# 512_outin_arduino.net
KiCad netlist of a schematic drawn in EAGLE
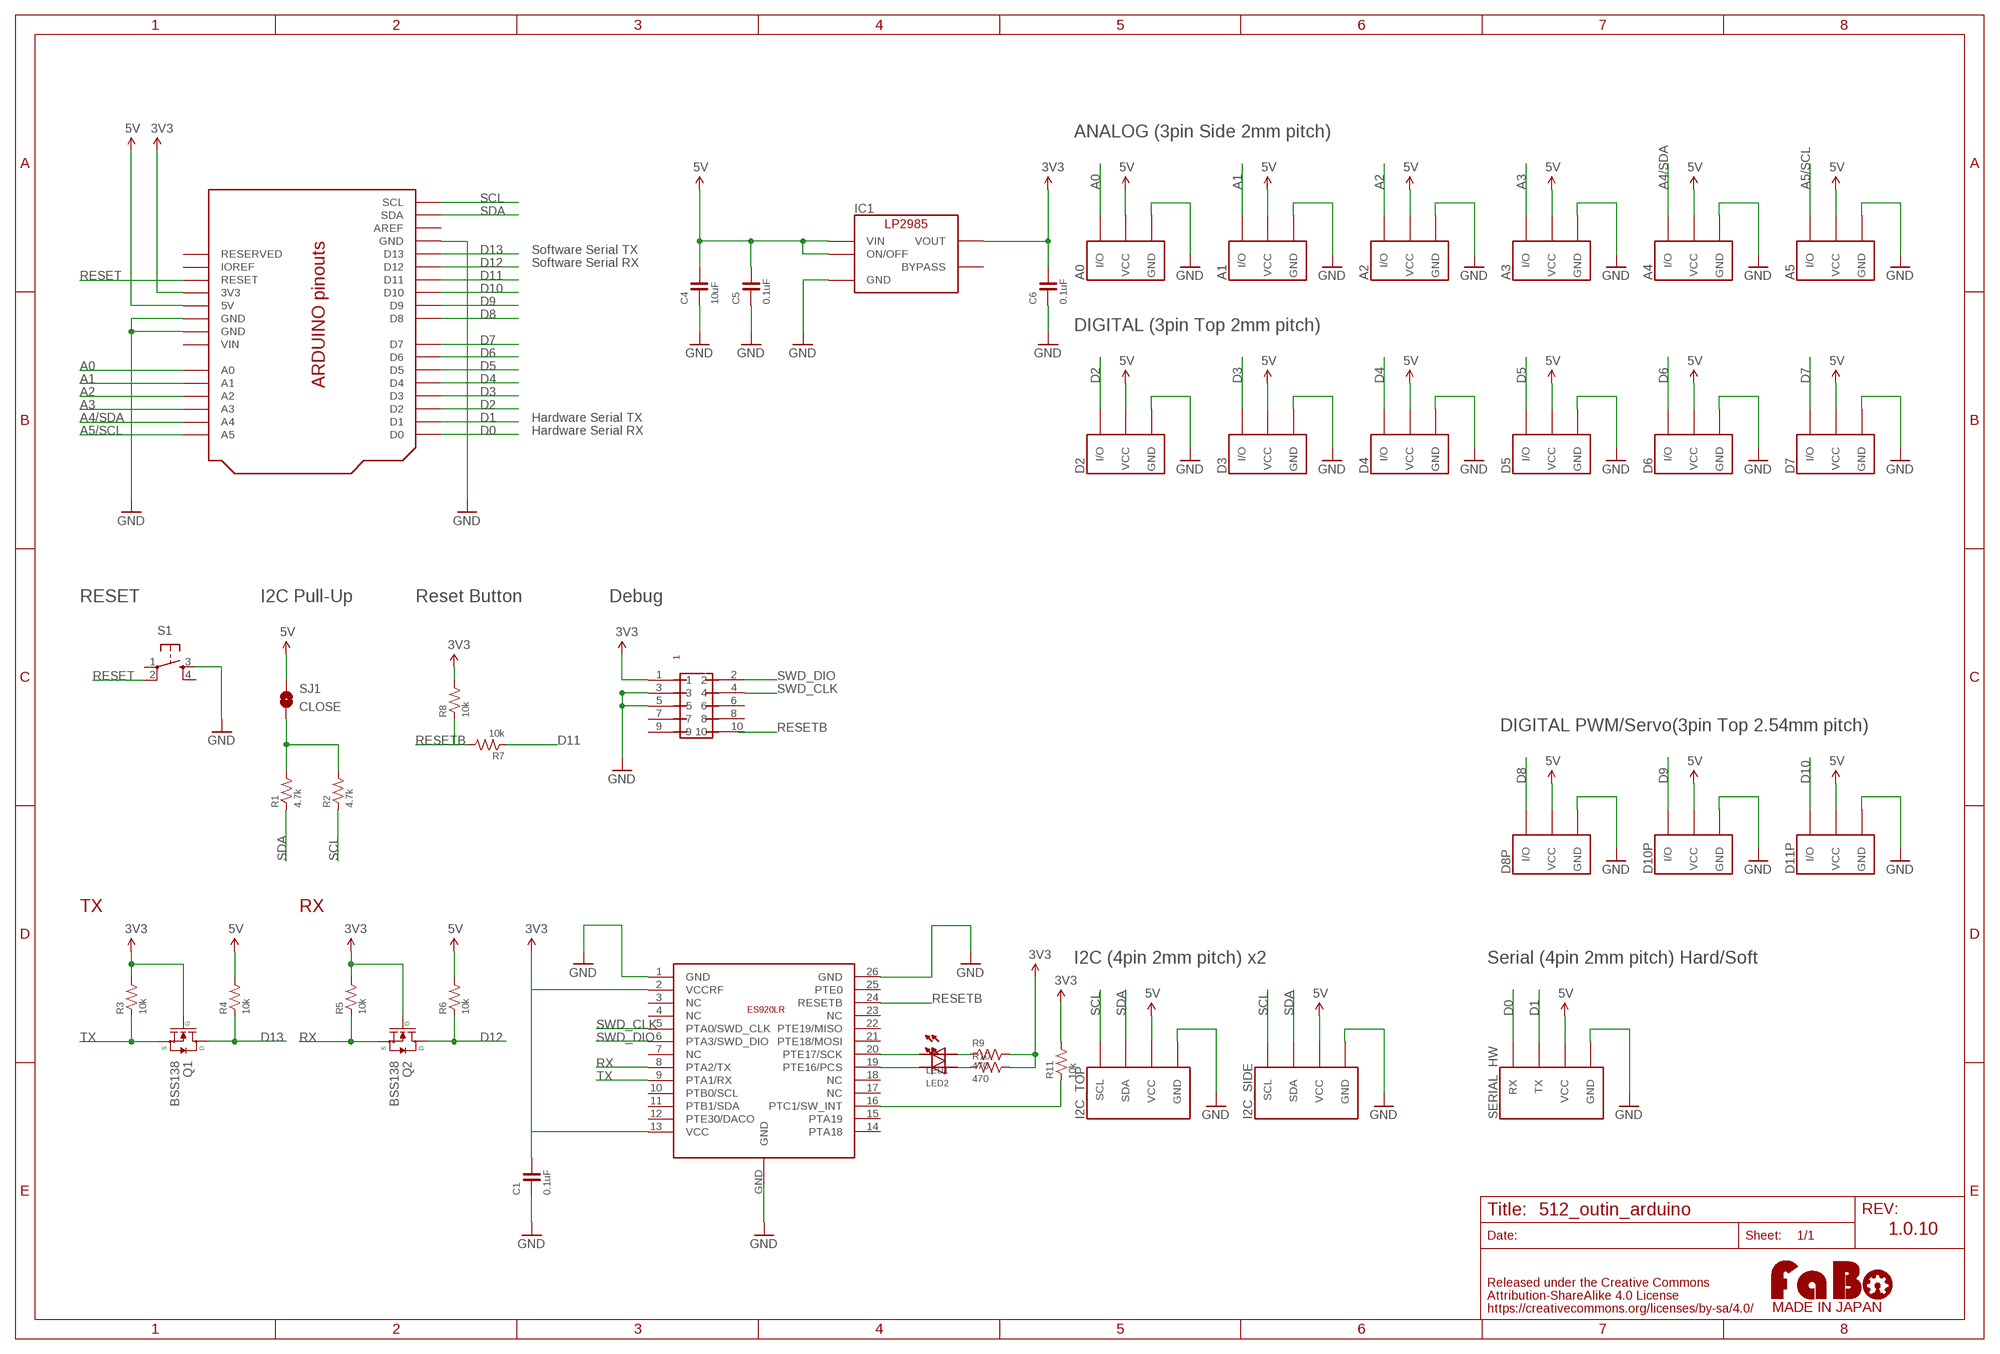
[diagram p0: schematic, sheet 1]

(export (version "E")
  (design (tool "Eeschema 10.0.6"))
  (components
    (comp (ref "A0")
      (value "FABO_BRICK_3PIN-S03B-PASK-2_LONG")
      (footprint "eagle-import:FABO_BRICK_3PIN_S03B-PASK-2_LONG")
      (libsource (lib "eagle-import") (part "FABO_BRICK_3PIN-S03B-PASK-2_LONG"))
    )
    (comp (ref "A1")
      (value "FABO_BRICK_3PIN-S03B-PASK-2_LONG")
      (footprint "eagle-import:FABO_BRICK_3PIN_S03B-PASK-2_LONG")
      (libsource (lib "eagle-import") (part "FABO_BRICK_3PIN-S03B-PASK-2_LONG"))
    )
    (comp (ref "A2")
      (value "FABO_BRICK_3PIN-S03B-PASK-2_LONG")
      (footprint "eagle-import:FABO_BRICK_3PIN_S03B-PASK-2_LONG")
      (libsource (lib "eagle-import") (part "FABO_BRICK_3PIN-S03B-PASK-2_LONG"))
    )
    (comp (ref "A3")
      (value "FABO_BRICK_3PIN-S03B-PASK-2_LONG")
      (footprint "eagle-import:FABO_BRICK_3PIN_S03B-PASK-2_LONG")
      (libsource (lib "eagle-import") (part "FABO_BRICK_3PIN-S03B-PASK-2_LONG"))
    )
    (comp (ref "A4")
      (value "FABO_BRICK_3PIN-S03B-PASK-2_LONG")
      (footprint "eagle-import:FABO_BRICK_3PIN_S03B-PASK-2_LONG")
      (libsource (lib "eagle-import") (part "FABO_BRICK_3PIN-S03B-PASK-2_LONG"))
    )
    (comp (ref "A5")
      (value "FABO_BRICK_3PIN-S03B-PASK-2_LONG")
      (footprint "eagle-import:FABO_BRICK_3PIN_S03B-PASK-2_LONG")
      (libsource (lib "eagle-import") (part "FABO_BRICK_3PIN-S03B-PASK-2_LONG"))
    )
    (comp (ref "C1")
      (value "0.1uF")
      (footprint "eagle-import:0603-NARROW")
      (libsource (lib "eagle-import") (part "CAPACITOR-0603_NARROW"))
    )
    (comp (ref "C4")
      (value "10uF")
      (footprint "eagle-import:0603-NARROW")
      (libsource (lib "eagle-import") (part "CAPACITOR-0603_NARROW"))
    )
    (comp (ref "C5")
      (value "0.1uF")
      (footprint "eagle-import:0603-NARROW")
      (libsource (lib "eagle-import") (part "CAPACITOR-0603_NARROW"))
    )
    (comp (ref "C6")
      (value "0.1uF")
      (footprint "eagle-import:0603-NARROW")
      (libsource (lib "eagle-import") (part "CAPACITOR-0603_NARROW"))
    )
    (comp (ref "D2")
      (value "FABO_BRICK_3PIN-B03B-PASK-1")
      (footprint "eagle-import:FABO_BRICK_3PIN_B03B-PASK-1")
      (libsource (lib "eagle-import") (part "FABO_BRICK_3PIN-B03B-PASK-1"))
    )
    (comp (ref "D3")
      (value "FABO_BRICK_3PIN-B03B-PASK-1")
      (footprint "eagle-import:FABO_BRICK_3PIN_B03B-PASK-1")
      (libsource (lib "eagle-import") (part "FABO_BRICK_3PIN-B03B-PASK-1"))
    )
    (comp (ref "D4")
      (value "FABO_BRICK_3PIN-B03B-PASK-1")
      (footprint "eagle-import:FABO_BRICK_3PIN_B03B-PASK-1")
      (libsource (lib "eagle-import") (part "FABO_BRICK_3PIN-B03B-PASK-1"))
    )
    (comp (ref "D5")
      (value "FABO_BRICK_3PIN-B03B-PASK-1")
      (footprint "eagle-import:FABO_BRICK_3PIN_B03B-PASK-1")
      (libsource (lib "eagle-import") (part "FABO_BRICK_3PIN-B03B-PASK-1"))
    )
    (comp (ref "D6")
      (value "FABO_BRICK_3PIN-B03B-PASK-1")
      (footprint "eagle-import:FABO_BRICK_3PIN_B03B-PASK-1")
      (libsource (lib "eagle-import") (part "FABO_BRICK_3PIN-B03B-PASK-1"))
    )
    (comp (ref "D7")
      (value "FABO_BRICK_3PIN-B03B-PASK-1")
      (footprint "eagle-import:FABO_BRICK_3PIN_B03B-PASK-1")
      (libsource (lib "eagle-import") (part "FABO_BRICK_3PIN-B03B-PASK-1"))
    )
    (comp (ref "D8P")
      (value "FABO_BRICK_3PIN-HEADER")
      (footprint "eagle-import:FABO_BRICK_3PIN_HEADER")
      (libsource (lib "eagle-import") (part "FABO_BRICK_3PIN-HEADER"))
    )
    (comp (ref "D10P")
      (value "FABO_BRICK_3PIN-HEADER")
      (footprint "eagle-import:FABO_BRICK_3PIN_HEADER")
      (libsource (lib "eagle-import") (part "FABO_BRICK_3PIN-HEADER"))
    )
    (comp (ref "D11P")
      (value "FABO_BRICK_3PIN-HEADER")
      (footprint "eagle-import:FABO_BRICK_3PIN_HEADER")
      (libsource (lib "eagle-import") (part "FABO_BRICK_3PIN-HEADER"))
    )
    (comp (ref "I2C_SIDE")
      (value "FABO_BRICK_I2C-S04B-PASK-2_LONG")
      (footprint "eagle-import:FABO_BRICK_I2C_S04B-PASK-2_LONG")
      (libsource (lib "eagle-import") (part "FABO_BRICK_I2C-S04B-PASK-2_LONG"))
    )
    (comp (ref "I2C_TOP")
      (value "FABO_BRICK_I2C-B04B-PASK-1")
      (footprint "eagle-import:FABO_BRICK_I2C_B04B-PASK-1")
      (libsource (lib "eagle-import") (part "FABO_BRICK_I2C-B04B-PASK-1"))
    )
    (comp (ref "IC1")
      (value "LP2985-33DBV")
      (footprint "eagle-import:SOT-23-5")
      (libsource (lib "eagle-import") (part "LP2985-33DBV"))
    )
    (comp (ref "LED1")
      (value "LED-0603")
      (footprint "eagle-import:0603")
      (libsource (lib "eagle-import") (part "LED-0603"))
    )
    (comp (ref "LED2")
      (value "LED-0603")
      (footprint "eagle-import:0603")
      (libsource (lib "eagle-import") (part "LED-0603"))
    )
    (comp (ref "Q1")
      (value "BSS138")
      (footprint "eagle-import:SOT23-3")
      (libsource (lib "eagle-import") (part "MOSFET-N"))
    )
    (comp (ref "Q2")
      (value "BSS138")
      (footprint "eagle-import:SOT23-3")
      (libsource (lib "eagle-import") (part "MOSFET-N"))
    )
    (comp (ref "R1")
      (value "4.7k")
      (footprint "eagle-import:0603")
      (libsource (lib "eagle-import") (part "RESISTOR-0603"))
    )
    (comp (ref "R2")
      (value "4.7k")
      (footprint "eagle-import:0603")
      (libsource (lib "eagle-import") (part "RESISTOR-0603"))
    )
    (comp (ref "R3")
      (value "10k")
      (footprint "eagle-import:0603-NARROW")
      (libsource (lib "eagle-import") (part "RESISTOR-0603-NARROW"))
    )
    (comp (ref "R4")
      (value "10k")
      (footprint "eagle-import:0603-NARROW")
      (libsource (lib "eagle-import") (part "RESISTOR-0603-NARROW"))
    )
    (comp (ref "R5")
      (value "10k")
      (footprint "eagle-import:0603-NARROW")
      (libsource (lib "eagle-import") (part "RESISTOR-0603-NARROW"))
    )
    (comp (ref "R6")
      (value "10k")
      (footprint "eagle-import:0603-NARROW")
      (libsource (lib "eagle-import") (part "RESISTOR-0603-NARROW"))
    )
    (comp (ref "R7")
      (value "10k")
      (footprint "eagle-import:0603-NARROW")
      (libsource (lib "eagle-import") (part "RESISTOR-0603-NARROW"))
    )
    (comp (ref "R8")
      (value "10k")
      (footprint "eagle-import:0603-NARROW")
      (libsource (lib "eagle-import") (part "RESISTOR-0603-NARROW"))
    )
    (comp (ref "R9")
      (value "470")
      (footprint "eagle-import:0603-NARROW")
      (libsource (lib "eagle-import") (part "RESISTOR-0603-NARROW"))
    )
    (comp (ref "R10")
      (value "470")
      (footprint "eagle-import:0603-NARROW")
      (libsource (lib "eagle-import") (part "RESISTOR-0603-NARROW"))
    )
    (comp (ref "R11")
      (value "10k")
      (footprint "eagle-import:0603-NARROW")
      (libsource (lib "eagle-import") (part "RESISTOR-0603-NARROW"))
    )
    (comp (ref "S1")
      (value "TACT-SWITCH-6MM")
      (footprint "eagle-import:DTS_6_V")
      (libsource (lib "eagle-import") (part "TACT-SWITCH-6MM"))
    )
    (comp (ref "SERIAL_HW")
      (value "FABO_BRICK_SERIAL-B04B-PASK-1")
      (footprint "eagle-import:FABO_BRICK_SERIAL_B04B-PASK-1")
      (libsource (lib "eagle-import") (part "FABO_BRICK_SERIAL-B04B-PASK-1"))
    )
    (comp (ref "SJ1")
      (value "CLOSE")
      (footprint "eagle-import:SMD-JUMPER-2-CLOSE")
      (libsource (lib "eagle-import") (part "SMD-JUMPER-2-CLOSE"))
    )
    (comp (ref "U$10")
      (value "LOGO_FABO-M")
      (footprint "eagle-import:LOGO_FABO_MS")
      (libsource (lib "eagle-import") (part "LOGO_FABO-M"))
    )
    (comp (ref "U$15")
      (value "PIN-HEADER-SMT(1.27MM)2X5")
      (footprint "eagle-import:PIN-HEADER-SMT(1.27MM)2X5")
      (libsource (lib "eagle-import") (part "PIN-HEADER-SMT(1.27MM)2X5"))
    )
    (comp (ref "U$16")
      (value "ES920LR")
      (footprint "eagle-import:ES920LR")
      (libsource (lib "eagle-import") (part "ES920LR"))
    )
    (comp (ref "U1")
      (value "ARDUINO_UNO_R3_SHIELD-OUTIN")
      (footprint "eagle-import:ARDUINO_SHIELD_OUTIN")
      (libsource (lib "eagle-import") (part "ARDUINO_UNO_R3_SHIELD-OUTIN"))
    )
  )
  (nets
    (net (code "1") (name "/A0") (class "Default")
      (node (ref "A0") (pin "I/O") (pinfunction "I/O_I/O") (pintype "bidirectional"))
      (node (ref "U1") (pin "A0") (pinfunction "A0_A0") (pintype "bidirectional"))
    )
    (net (code "2") (name "/A1") (class "Default")
      (node (ref "A1") (pin "I/O") (pinfunction "I/O_I/O") (pintype "bidirectional"))
      (node (ref "U1") (pin "A1") (pinfunction "A1_A1") (pintype "bidirectional"))
    )
    (net (code "3") (name "/A2") (class "Default")
      (node (ref "A2") (pin "I/O") (pinfunction "I/O_I/O") (pintype "bidirectional"))
      (node (ref "U1") (pin "A2") (pinfunction "A2_A2") (pintype "bidirectional"))
    )
    (net (code "4") (name "/A3") (class "Default")
      (node (ref "A3") (pin "I/O") (pinfunction "I/O_I/O") (pintype "bidirectional"))
      (node (ref "U1") (pin "A3") (pinfunction "A3_A3") (pintype "bidirectional"))
    )
    (net (code "5") (name "/A4{slash}SDA") (class "Default")
      (node (ref "A4") (pin "I/O") (pinfunction "I/O_I/O") (pintype "bidirectional"))
      (node (ref "U1") (pin "A4") (pinfunction "A4_A4") (pintype "bidirectional"))
    )
    (net (code "6") (name "/A5{slash}SCL") (class "Default")
      (node (ref "A5") (pin "I/O") (pinfunction "I/O_I/O") (pintype "bidirectional"))
      (node (ref "U1") (pin "A5") (pinfunction "A5_A5") (pintype "bidirectional"))
    )
    (net (code "7") (name "/D0") (class "Default")
      (node (ref "SERIAL_HW") (pin "RX") (pinfunction "RX_RX") (pintype "bidirectional"))
      (node (ref "U1") (pin "D0") (pinfunction "D0_D0") (pintype "bidirectional"))
    )
    (net (code "8") (name "/D1") (class "Default")
      (node (ref "SERIAL_HW") (pin "TX") (pinfunction "TX_TX") (pintype "bidirectional"))
      (node (ref "U1") (pin "D1") (pinfunction "D1_D1") (pintype "bidirectional"))
    )
    (net (code "9") (name "/D2") (class "Default")
      (node (ref "D2") (pin "I/O") (pinfunction "I/O_I/O") (pintype "bidirectional"))
      (node (ref "U1") (pin "D2") (pinfunction "D2_D2") (pintype "bidirectional"))
    )
    (net (code "10") (name "/D3") (class "Default")
      (node (ref "D3") (pin "I/O") (pinfunction "I/O_I/O") (pintype "bidirectional"))
      (node (ref "U1") (pin "D3") (pinfunction "D3_D3") (pintype "bidirectional"))
    )
    (net (code "11") (name "/D4") (class "Default")
      (node (ref "D4") (pin "I/O") (pinfunction "I/O_I/O") (pintype "bidirectional"))
      (node (ref "U1") (pin "D4") (pinfunction "D4_D4") (pintype "bidirectional"))
    )
    (net (code "12") (name "/D5") (class "Default")
      (node (ref "D5") (pin "I/O") (pinfunction "I/O_I/O") (pintype "bidirectional"))
      (node (ref "U1") (pin "D5") (pinfunction "D5_D5") (pintype "bidirectional"))
    )
    (net (code "13") (name "/D6") (class "Default")
      (node (ref "D6") (pin "I/O") (pinfunction "I/O_I/O") (pintype "bidirectional"))
      (node (ref "U1") (pin "D6") (pinfunction "D6_D6") (pintype "bidirectional"))
    )
    (net (code "14") (name "/D7") (class "Default")
      (node (ref "D7") (pin "I/O") (pinfunction "I/O_I/O") (pintype "bidirectional"))
      (node (ref "U1") (pin "D7") (pinfunction "D7_D7") (pintype "bidirectional"))
    )
    (net (code "15") (name "/D8") (class "Default")
      (node (ref "D8P") (pin "I/O") (pinfunction "I/O_I/O") (pintype "bidirectional"))
      (node (ref "U1") (pin "D8") (pinfunction "D8_D8") (pintype "bidirectional"))
    )
    (net (code "16") (name "/D9") (class "Default")
      (node (ref "D10P") (pin "I/O") (pinfunction "I/O_I/O") (pintype "bidirectional"))
      (node (ref "U1") (pin "D9") (pinfunction "D9_D9") (pintype "bidirectional"))
    )
    (net (code "17") (name "/D10") (class "Default")
      (node (ref "D11P") (pin "I/O") (pinfunction "I/O_I/O") (pintype "bidirectional"))
      (node (ref "U1") (pin "D10") (pinfunction "D10_D10") (pintype "bidirectional"))
    )
    (net (code "18") (name "/D11") (class "Default")
      (node (ref "R7") (pin "1") (pinfunction "1_1") (pintype "bidirectional"))
      (node (ref "U1") (pin "D11") (pinfunction "D11_D11") (pintype "bidirectional"))
    )
    (net (code "19") (name "/D12") (class "Default")
      (node (ref "Q2") (pin "3") (pinfunction "D_3") (pintype "passive"))
      (node (ref "R6") (pin "1") (pinfunction "1_1") (pintype "bidirectional"))
      (node (ref "U1") (pin "D12") (pinfunction "D12_D12") (pintype "bidirectional"))
    )
    (net (code "20") (name "/D13") (class "Default")
      (node (ref "Q1") (pin "3") (pinfunction "D_3") (pintype "passive"))
      (node (ref "R4") (pin "1") (pinfunction "1_1") (pintype "bidirectional"))
      (node (ref "U1") (pin "D13") (pinfunction "D13_D13") (pintype "bidirectional"))
    )
    (net (code "21") (name "/RESET") (class "Default")
      (node (ref "S1") (pin "2") (pinfunction "2_2") (pintype "passive"))
      (node (ref "U1") (pin "RESET") (pinfunction "RESET_RESET") (pintype "bidirectional"))
    )
    (net (code "22") (name "/RESETB") (class "Default")
      (node (ref "R7") (pin "2") (pinfunction "2_2") (pintype "bidirectional"))
      (node (ref "R8") (pin "1") (pinfunction "1_1") (pintype "bidirectional"))
      (node (ref "U$15") (pin "10") (pinfunction "10_10") (pintype "bidirectional"))
      (node (ref "U$16") (pin "24") (pinfunction "RESETB_24") (pintype "bidirectional"))
    )
    (net (code "23") (name "/RX") (class "Default")
      (node (ref "Q2") (pin "2") (pinfunction "S_2") (pintype "passive"))
      (node (ref "R5") (pin "1") (pinfunction "1_1") (pintype "bidirectional"))
      (node (ref "U$16") (pin "8") (pinfunction "PTA2/TX_8") (pintype "bidirectional"))
    )
    (net (code "24") (name "/SCL") (class "Default")
      (node (ref "I2C_SIDE") (pin "SCL") (pinfunction "SCL_SCL") (pintype "bidirectional"))
      (node (ref "I2C_TOP") (pin "SCL") (pinfunction "SCL_SCL") (pintype "bidirectional"))
      (node (ref "R2") (pin "1") (pinfunction "1_1") (pintype "bidirectional"))
      (node (ref "U1") (pin "SCL") (pinfunction "SCL_SCL") (pintype "bidirectional"))
    )
    (net (code "25") (name "/SDA") (class "Default")
      (node (ref "I2C_SIDE") (pin "SDA") (pinfunction "SDA_SDA") (pintype "bidirectional"))
      (node (ref "I2C_TOP") (pin "SDA") (pinfunction "SDA_SDA") (pintype "bidirectional"))
      (node (ref "R1") (pin "1") (pinfunction "1_1") (pintype "bidirectional"))
      (node (ref "U1") (pin "SDA") (pinfunction "SDA_SDA") (pintype "bidirectional"))
    )
    (net (code "26") (name "/SWD_CLK") (class "Default")
      (node (ref "U$15") (pin "4") (pinfunction "4_4") (pintype "bidirectional"))
      (node (ref "U$16") (pin "5") (pinfunction "PTA0/SWD_CLK_5") (pintype "bidirectional"))
    )
    (net (code "27") (name "/SWD_DIO") (class "Default")
      (node (ref "U$15") (pin "2") (pinfunction "2_2") (pintype "bidirectional"))
      (node (ref "U$16") (pin "6") (pinfunction "PTA3/SWD_DIO_6") (pintype "bidirectional"))
    )
    (net (code "28") (name "/TX") (class "Default")
      (node (ref "Q1") (pin "2") (pinfunction "S_2") (pintype "passive"))
      (node (ref "R3") (pin "1") (pinfunction "1_1") (pintype "bidirectional"))
      (node (ref "U$16") (pin "9") (pinfunction "PTA1/RX_9") (pintype "bidirectional"))
    )
    (net (code "29") (name "/VIN") (class "Default")
      (node (ref "U1") (pin "VIN") (pinfunction "VIN_VIN") (pintype "power_in"))
    )
    (net (code "30") (name "3V3") (class "Default")
      (node (ref "C1") (pin "2") (pinfunction "2_2") (pintype "passive"))
      (node (ref "C6") (pin "2") (pinfunction "2_2") (pintype "passive"))
      (node (ref "IC1") (pin "5") (pinfunction "VOUT_5") (pintype "output"))
      (node (ref "Q1") (pin "1") (pinfunction "G_1") (pintype "passive"))
      (node (ref "Q2") (pin "1") (pinfunction "G_1") (pintype "passive"))
      (node (ref "R10") (pin "2") (pinfunction "2_2") (pintype "bidirectional"))
      (node (ref "R11") (pin "2") (pinfunction "2_2") (pintype "bidirectional"))
      (node (ref "R3") (pin "2") (pinfunction "2_2") (pintype "bidirectional"))
      (node (ref "R5") (pin "2") (pinfunction "2_2") (pintype "bidirectional"))
      (node (ref "R8") (pin "2") (pinfunction "2_2") (pintype "bidirectional"))
      (node (ref "R9") (pin "2") (pinfunction "2_2") (pintype "bidirectional"))
      (node (ref "U$15") (pin "1") (pinfunction "1_1") (pintype "bidirectional"))
      (node (ref "U$16") (pin "13") (pinfunction "VCC_13") (pintype "bidirectional"))
      (node (ref "U$16") (pin "2") (pinfunction "VCCRF_2") (pintype "bidirectional"))
      (node (ref "U1") (pin "3V3") (pinfunction "3V3_3V3") (pintype "power_in"))
    )
    (net (code "31") (name "5V") (class "Default")
      (node (ref "A0") (pin "VCC") (pinfunction "VCC_VCC") (pintype "bidirectional"))
      (node (ref "A1") (pin "VCC") (pinfunction "VCC_VCC") (pintype "bidirectional"))
      (node (ref "A2") (pin "VCC") (pinfunction "VCC_VCC") (pintype "bidirectional"))
      (node (ref "A3") (pin "VCC") (pinfunction "VCC_VCC") (pintype "bidirectional"))
      (node (ref "A4") (pin "VCC") (pinfunction "VCC_VCC") (pintype "bidirectional"))
      (node (ref "A5") (pin "VCC") (pinfunction "VCC_VCC") (pintype "bidirectional"))
      (node (ref "C4") (pin "2") (pinfunction "2_2") (pintype "passive"))
      (node (ref "C5") (pin "2") (pinfunction "2_2") (pintype "passive"))
      (node (ref "D10P") (pin "VCC") (pinfunction "VCC_VCC") (pintype "bidirectional"))
      (node (ref "D11P") (pin "VCC") (pinfunction "VCC_VCC") (pintype "bidirectional"))
      (node (ref "D2") (pin "VCC") (pinfunction "VCC_VCC") (pintype "bidirectional"))
      (node (ref "D3") (pin "VCC") (pinfunction "VCC_VCC") (pintype "bidirectional"))
      (node (ref "D4") (pin "VCC") (pinfunction "VCC_VCC") (pintype "bidirectional"))
      (node (ref "D5") (pin "VCC") (pinfunction "VCC_VCC") (pintype "bidirectional"))
      (node (ref "D6") (pin "VCC") (pinfunction "VCC_VCC") (pintype "bidirectional"))
      (node (ref "D7") (pin "VCC") (pinfunction "VCC_VCC") (pintype "bidirectional"))
      (node (ref "D8P") (pin "VCC") (pinfunction "VCC_VCC") (pintype "bidirectional"))
      (node (ref "I2C_SIDE") (pin "VCC") (pinfunction "VCC_VCC") (pintype "bidirectional"))
      (node (ref "I2C_TOP") (pin "VCC") (pinfunction "VCC_VCC") (pintype "bidirectional"))
      (node (ref "IC1") (pin "1") (pinfunction "VIN_1") (pintype "input"))
      (node (ref "IC1") (pin "3") (pinfunction "ON/OFF_3") (pintype "input"))
      (node (ref "R4") (pin "2") (pinfunction "2_2") (pintype "bidirectional"))
      (node (ref "R6") (pin "2") (pinfunction "2_2") (pintype "bidirectional"))
      (node (ref "SERIAL_HW") (pin "VCC") (pinfunction "VCC_VCC") (pintype "bidirectional"))
      (node (ref "SJ1") (pin "1") (pinfunction "1_1") (pintype "passive"))
      (node (ref "U1") (pin "5V") (pinfunction "5V_5V") (pintype "power_in"))
    )
    (net (code "32") (name "GND") (class "Default")
      (node (ref "A0") (pin "GND") (pinfunction "GND_GND") (pintype "bidirectional"))
      (node (ref "A1") (pin "GND") (pinfunction "GND_GND") (pintype "bidirectional"))
      (node (ref "A2") (pin "GND") (pinfunction "GND_GND") (pintype "bidirectional"))
      (node (ref "A3") (pin "GND") (pinfunction "GND_GND") (pintype "bidirectional"))
      (node (ref "A4") (pin "GND") (pinfunction "GND_GND") (pintype "bidirectional"))
      (node (ref "A5") (pin "GND") (pinfunction "GND_GND") (pintype "bidirectional"))
      (node (ref "C1") (pin "1") (pinfunction "1_1") (pintype "passive"))
      (node (ref "C4") (pin "1") (pinfunction "1_1") (pintype "passive"))
      (node (ref "C5") (pin "1") (pinfunction "1_1") (pintype "passive"))
      (node (ref "C6") (pin "1") (pinfunction "1_1") (pintype "passive"))
      (node (ref "D10P") (pin "GND") (pinfunction "GND_GND") (pintype "bidirectional"))
      (node (ref "D11P") (pin "GND") (pinfunction "GND_GND") (pintype "bidirectional"))
      (node (ref "D2") (pin "GND") (pinfunction "GND_GND") (pintype "bidirectional"))
      (node (ref "D3") (pin "GND") (pinfunction "GND_GND") (pintype "bidirectional"))
      (node (ref "D4") (pin "GND") (pinfunction "GND_GND") (pintype "bidirectional"))
      (node (ref "D5") (pin "GND") (pinfunction "GND_GND") (pintype "bidirectional"))
      (node (ref "D6") (pin "GND") (pinfunction "GND_GND") (pintype "bidirectional"))
      (node (ref "D7") (pin "GND") (pinfunction "GND_GND") (pintype "bidirectional"))
      (node (ref "D8P") (pin "GND") (pinfunction "GND_GND") (pintype "bidirectional"))
      (node (ref "I2C_SIDE") (pin "GND") (pinfunction "GND_GND") (pintype "bidirectional"))
      (node (ref "I2C_TOP") (pin "GND") (pinfunction "GND_GND") (pintype "bidirectional"))
      (node (ref "IC1") (pin "2") (pinfunction "GND_2") (pintype "power_in"))
      (node (ref "S1") (pin "3") (pinfunction "3_3") (pintype "passive"))
      (node (ref "SERIAL_HW") (pin "GND") (pinfunction "GND_GND") (pintype "bidirectional"))
      (node (ref "U$15") (pin "3") (pinfunction "3_3") (pintype "bidirectional"))
      (node (ref "U$15") (pin "5") (pinfunction "5_5") (pintype "bidirectional"))
      (node (ref "U$16") (pin "1") (pinfunction "GND_1") (pintype "bidirectional"))
      (node (ref "U$16") (pin "26") (pinfunction "GND_26") (pintype "bidirectional"))
      (node (ref "U$16") (pin "GND") (pinfunction "GND_GND") (pintype "bidirectional"))
      (node (ref "U1") (pin "GND1") (pinfunction "GND_GND1") (pintype "power_in"))
      (node (ref "U1") (pin "GND2") (pinfunction "GND_GND2") (pintype "power_in"))
      (node (ref "U1") (pin "GND3") (pinfunction "GND_GND3") (pintype "power_in"))
    )
    (net (code "33") (name "Net-(LED1-PadANODE)") (class "Default")
      (node (ref "LED1") (pin "ANODE") (pinfunction "ANODE_ANODE") (pintype "passive"))
      (node (ref "R9") (pin "1") (pinfunction "1_1") (pintype "bidirectional"))
    )
    (net (code "34") (name "Net-(LED2-PadANODE)") (class "Default")
      (node (ref "LED2") (pin "ANODE") (pinfunction "ANODE_ANODE") (pintype "passive"))
      (node (ref "R10") (pin "1") (pinfunction "1_1") (pintype "bidirectional"))
    )
    (net (code "35") (name "Net-(R1-Pad2)") (class "Default")
      (node (ref "R1") (pin "2") (pinfunction "2_2") (pintype "bidirectional"))
      (node (ref "R2") (pin "2") (pinfunction "2_2") (pintype "bidirectional"))
      (node (ref "SJ1") (pin "2") (pinfunction "2_2") (pintype "passive"))
    )
    (net (code "36") (name "Net-(U$16-PTC1{slash}SW_INT)") (class "Default")
      (node (ref "R11") (pin "1") (pinfunction "1_1") (pintype "bidirectional"))
      (node (ref "U$16") (pin "16") (pinfunction "PTC1/SW_INT_16") (pintype "bidirectional"))
    )
    (net (code "37") (name "Net-(U$16-PTE16{slash}PCS)") (class "Default")
      (node (ref "LED2") (pin "CATHODE") (pinfunction "CATHODE_CATHODE") (pintype "passive"))
      (node (ref "U$16") (pin "19") (pinfunction "PTE16/PCS_19") (pintype "bidirectional"))
    )
    (net (code "38") (name "Net-(U$16-PTE17{slash}SCK)") (class "Default")
      (node (ref "LED1") (pin "CATHODE") (pinfunction "CATHODE_CATHODE") (pintype "passive"))
      (node (ref "U$16") (pin "20") (pinfunction "PTE17/SCK_20") (pintype "bidirectional"))
    )
    (net (code "39") (name "unconnected-(IC1-BYPASS-Pad4)") (class "Default")
      (node (ref "IC1") (pin "4") (pinfunction "BYPASS_4") (pintype "bidirectional"))
    )
    (net (code "40") (name "unconnected-(S1-Pad1)") (class "Default")
      (node (ref "S1") (pin "1") (pinfunction "1_1") (pintype "passive"))
    )
    (net (code "41") (name "unconnected-(S1-Pad4)") (class "Default")
      (node (ref "S1") (pin "4") (pinfunction "4_4") (pintype "passive"))
    )
    (net (code "42") (name "unconnected-(U$15-Pad6)") (class "Default")
      (node (ref "U$15") (pin "6") (pinfunction "6_6") (pintype "bidirectional"))
    )
    (net (code "43") (name "unconnected-(U$15-Pad7)") (class "Default")
      (node (ref "U$15") (pin "7") (pinfunction "7_7") (pintype "bidirectional"))
    )
    (net (code "44") (name "unconnected-(U$15-Pad8)") (class "Default")
      (node (ref "U$15") (pin "8") (pinfunction "8_8") (pintype "bidirectional"))
    )
    (net (code "45") (name "unconnected-(U$15-Pad9)") (class "Default")
      (node (ref "U$15") (pin "9") (pinfunction "9_9") (pintype "bidirectional"))
    )
    (net (code "46") (name "unconnected-(U$16-NC-Pad3)") (class "Default")
      (node (ref "U$16") (pin "3") (pinfunction "NC_3") (pintype "bidirectional"))
    )
    (net (code "47") (name "unconnected-(U$16-NC-Pad4)") (class "Default")
      (node (ref "U$16") (pin "4") (pinfunction "NC_4") (pintype "bidirectional"))
    )
    (net (code "48") (name "unconnected-(U$16-NC-Pad7)") (class "Default")
      (node (ref "U$16") (pin "7") (pinfunction "NC_7") (pintype "bidirectional"))
    )
    (net (code "49") (name "unconnected-(U$16-NC-Pad17)") (class "Default")
      (node (ref "U$16") (pin "17") (pinfunction "NC_17") (pintype "bidirectional"))
    )
    (net (code "50") (name "unconnected-(U$16-NC-Pad18)") (class "Default")
      (node (ref "U$16") (pin "18") (pinfunction "NC_18") (pintype "bidirectional"))
    )
    (net (code "51") (name "unconnected-(U$16-NC-Pad23)") (class "Default")
      (node (ref "U$16") (pin "23") (pinfunction "NC_23") (pintype "bidirectional"))
    )
    (net (code "52") (name "unconnected-(U$16-PTA18-Pad14)") (class "Default")
      (node (ref "U$16") (pin "14") (pinfunction "PTA18_14") (pintype "bidirectional"))
    )
    (net (code "53") (name "unconnected-(U$16-PTA19-Pad15)") (class "Default")
      (node (ref "U$16") (pin "15") (pinfunction "PTA19_15") (pintype "bidirectional"))
    )
    (net (code "54") (name "unconnected-(U$16-PTB0{slash}SCL-Pad10)") (class "Default")
      (node (ref "U$16") (pin "10") (pinfunction "PTB0/SCL_10") (pintype "bidirectional"))
    )
    (net (code "55") (name "unconnected-(U$16-PTB1{slash}SDA-Pad11)") (class "Default")
      (node (ref "U$16") (pin "11") (pinfunction "PTB1/SDA_11") (pintype "bidirectional"))
    )
    (net (code "56") (name "unconnected-(U$16-PTE0-Pad25)") (class "Default")
      (node (ref "U$16") (pin "25") (pinfunction "PTE0_25") (pintype "bidirectional"))
    )
    (net (code "57") (name "unconnected-(U$16-PTE18{slash}MOSI-Pad21)") (class "Default")
      (node (ref "U$16") (pin "21") (pinfunction "PTE18/MOSI_21") (pintype "bidirectional"))
    )
    (net (code "58") (name "unconnected-(U$16-PTE19{slash}MISO-Pad22)") (class "Default")
      (node (ref "U$16") (pin "22") (pinfunction "PTE19/MISO_22") (pintype "bidirectional"))
    )
    (net (code "59") (name "unconnected-(U$16-PTE30{slash}DACO-Pad12)") (class "Default")
      (node (ref "U$16") (pin "12") (pinfunction "PTE30/DACO_12") (pintype "bidirectional"))
    )
    (net (code "60") (name "unconnected-(U1-PadAREF)") (class "Default")
      (node (ref "U1") (pin "AREF") (pinfunction "AREF_AREF") (pintype "bidirectional"))
    )
    (net (code "61") (name "unconnected-(U1-PadIOREF)") (class "Default")
      (node (ref "U1") (pin "IOREF") (pinfunction "IOREF_IOREF") (pintype "output"))
    )
    (net (code "62") (name "unconnected-(U1-PadRESERVED)") (class "Default")
      (node (ref "U1") (pin "RESERVED") (pinfunction "RESERVED_RESERVED") (pintype "no_connect"))
    )
  )
)
